# relayBoardSMD_RelayBottom.net
KiCad netlist of a schematic drawn in EAGLE
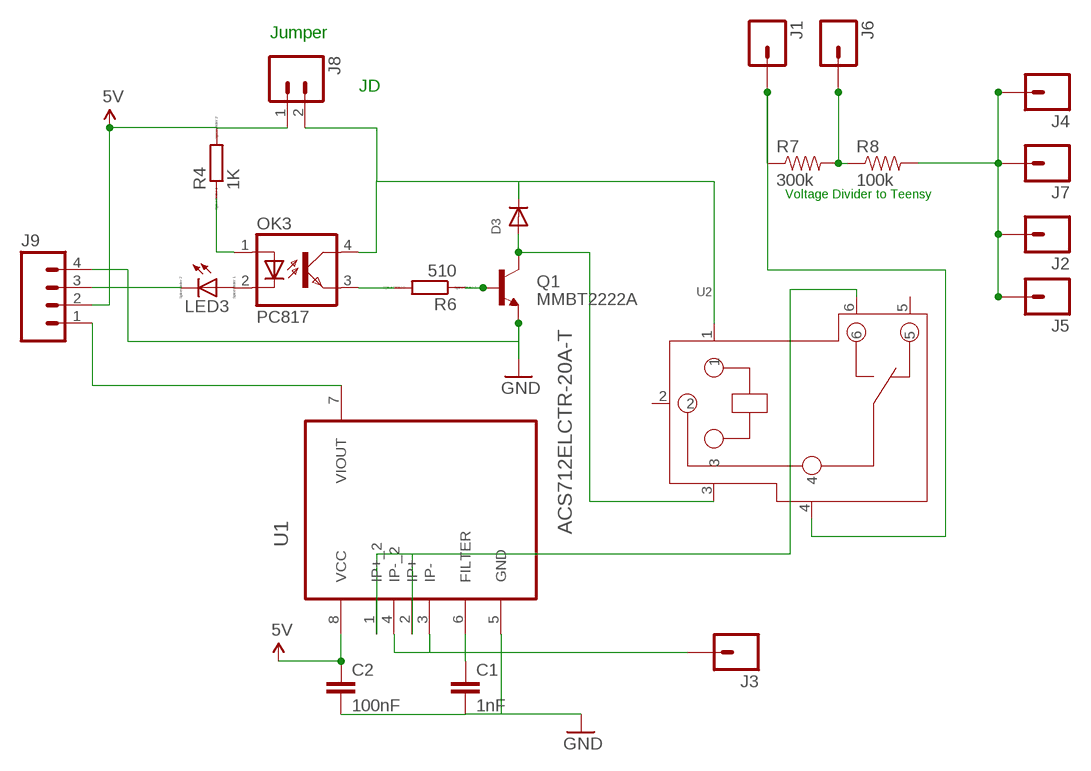
[diagram p0: schematic, sheet 1]

(export (version "E")
  (design (tool "Eeschema 10.0.6"))
  (components
    (comp (ref "C1")
      (value "1nF")
      (footprint "eagle-import:1206")
      (libsource (lib "eagle-import") (part "CAP1206"))
    )
    (comp (ref "C2")
      (value "100nF")
      (footprint "eagle-import:1206")
      (libsource (lib "eagle-import") (part "CAP1206"))
    )
    (comp (ref "D3")
      (value "DIODEDO-1N4148")
      (footprint "eagle-import:DO-1N4148")
      (libsource (lib "eagle-import") (part "DIODEDO-1N4148"))
    )
    (comp (ref "J1")
      (value "M01NOSILK-KIT")
      (footprint "eagle-import:1X01NS-KIT")
      (libsource (lib "eagle-import") (part "M01NOSILK-KIT"))
    )
    (comp (ref "J2")
      (value "M01NOSILK-KIT")
      (footprint "eagle-import:1X01NS-KIT")
      (libsource (lib "eagle-import") (part "M01NOSILK-KIT"))
    )
    (comp (ref "J3")
      (value "M01NOSILK-KIT")
      (footprint "eagle-import:1X01NS-KIT")
      (libsource (lib "eagle-import") (part "M01NOSILK-KIT"))
    )
    (comp (ref "J4")
      (value "M01NOSILK-KIT")
      (footprint "eagle-import:1X01NS-KIT")
      (libsource (lib "eagle-import") (part "M01NOSILK-KIT"))
    )
    (comp (ref "J5")
      (value "M01NOSILK-KIT")
      (footprint "eagle-import:1X01NS-KIT")
      (libsource (lib "eagle-import") (part "M01NOSILK-KIT"))
    )
    (comp (ref "J6")
      (value "M01NOSILK-KIT")
      (footprint "eagle-import:1X01NS-KIT")
      (libsource (lib "eagle-import") (part "M01NOSILK-KIT"))
    )
    (comp (ref "J7")
      (value "M01NOSILK-KIT")
      (footprint "eagle-import:1X01NS-KIT")
      (libsource (lib "eagle-import") (part "M01NOSILK-KIT"))
    )
    (comp (ref "J8")
      (value "M02LOCK_LONGPADS")
      (footprint "eagle-import:1X02_LOCK_LONGPADS")
      (libsource (lib "eagle-import") (part "M02LOCK_LONGPADS"))
    )
    (comp (ref "J9")
      (value "M04LOCK_LONGPADS")
      (footprint "eagle-import:1X04_LOCK_LONGPADS")
      (libsource (lib "eagle-import") (part "M04LOCK_LONGPADS"))
    )
    (comp (ref "LED3")
      (value "LED_E")
      (footprint "eagle-import:LED_1206")
      (libsource (lib "eagle-import") (part "LED_E"))
    )
    (comp (ref "OK3")
      (value "PC817")
      (footprint "eagle-import:DIL04")
      (fields (field (name "MPN") "PC817X4J000F"))
      (libsource (lib "eagle-import") (part "PC817"))
    )
    (comp (ref "Q1")
      (value "MMBT2222A")
      (footprint "eagle-import:SOT23-3")
      (libsource (lib "eagle-import") (part "TRANSISTOR_NPNMMBT2222A"))
    )
    (comp (ref "R4")
      (value "1K")
      (footprint "eagle-import:R1206")
      (libsource (lib "eagle-import") (part "RR1206"))
    )
    (comp (ref "R6")
      (value "510")
      (footprint "eagle-import:R1206")
      (libsource (lib "eagle-import") (part "RR1206"))
    )
    (comp (ref "R7")
      (value "300k")
      (footprint "eagle-import:1206")
      (libsource (lib "eagle-import") (part "RESISTOR1206"))
    )
    (comp (ref "R8")
      (value "100k")
      (footprint "eagle-import:1206")
      (libsource (lib "eagle-import") (part "RESISTOR1206"))
    )
    (comp (ref "U1")
      (value "ACS712ELCTR-20A-T")
      (footprint "eagle-import:SOIC127P600X175-8N")
      (libsource (lib "eagle-import") (part "ACS712ELCTR-20A-T"))
    )
    (comp (ref "U2")
      (value "RELAY-SLA-05VDC-SL-C")
      (footprint "eagle-import:6P-19.8H")
      (libsource (lib "eagle-import") (part "RELAY-SLA-05VDC-SL-C"))
    )
  )
  (nets
    (net (code "1") (name "5V") (class "Default")
      (node (ref "C2") (pin "1") (pinfunction "1_1") (pintype "passive"))
      (node (ref "J8") (pin "1") (pinfunction "1_1") (pintype "passive"))
      (node (ref "J9") (pin "2") (pinfunction "2_2") (pintype "passive"))
      (node (ref "R4") (pin "2") (pinfunction "2_2") (pintype "passive"))
      (node (ref "U1") (pin "8") (pinfunction "VCC_8") (pintype "power_in"))
    )
    (net (code "2") (name "GND") (class "Default")
      (node (ref "C1") (pin "2") (pinfunction "2_2") (pintype "passive"))
      (node (ref "C2") (pin "2") (pinfunction "2_2") (pintype "passive"))
      (node (ref "J9") (pin "4") (pinfunction "4_4") (pintype "passive"))
      (node (ref "Q1") (pin "2") (pinfunction "E_2") (pintype "passive"))
      (node (ref "U1") (pin "5") (pinfunction "GND_5") (pintype "passive"))
    )
    (net (code "3") (name "Net-(J1-Pad1)") (class "Default")
      (node (ref "J1") (pin "1") (pinfunction "1_1") (pintype "passive"))
      (node (ref "R7") (pin "1") (pinfunction "1_1") (pintype "passive"))
      (node (ref "U2") (pin "4") (pinfunction "4_4") (pintype "bidirectional"))
    )
    (net (code "4") (name "Net-(J2-Pad1)") (class "Default")
      (node (ref "J2") (pin "1") (pinfunction "1_1") (pintype "passive"))
      (node (ref "J4") (pin "1") (pinfunction "1_1") (pintype "passive"))
      (node (ref "J5") (pin "1") (pinfunction "1_1") (pintype "passive"))
      (node (ref "J7") (pin "1") (pinfunction "1_1") (pintype "passive"))
      (node (ref "R8") (pin "2") (pinfunction "2_2") (pintype "passive"))
    )
    (net (code "5") (name "Net-(J6-Pad1)") (class "Default")
      (node (ref "J6") (pin "1") (pinfunction "1_1") (pintype "passive"))
      (node (ref "R7") (pin "2") (pinfunction "2_2") (pintype "passive"))
      (node (ref "R8") (pin "1") (pinfunction "1_1") (pintype "passive"))
    )
    (net (code "6") (name "Net-(J9-Pad3)") (class "Default")
      (node (ref "J9") (pin "3") (pinfunction "3_3") (pintype "passive"))
      (node (ref "LED3") (pin "C") (pinfunction "C_C") (pintype "passive"))
    )
    (net (code "7") (name "Net-(OK3-A)") (class "Default")
      (node (ref "OK3") (pin "1") (pinfunction "A_1") (pintype "passive"))
      (node (ref "R4") (pin "1") (pinfunction "1_1") (pintype "passive"))
    )
    (net (code "8") (name "Net-(OK3-C)") (class "Default")
      (node (ref "LED3") (pin "A") (pinfunction "A_A") (pintype "passive"))
      (node (ref "OK3") (pin "2") (pinfunction "C_2") (pintype "passive"))
    )
    (net (code "9") (name "Net-(OK3-COL)") (class "Default")
      (node (ref "D3") (pin "C") (pinfunction "C_C") (pintype "passive"))
      (node (ref "J8") (pin "2") (pinfunction "2_2") (pintype "passive"))
      (node (ref "OK3") (pin "4") (pinfunction "COL_4") (pintype "passive"))
      (node (ref "U2") (pin "1") (pinfunction "1_1") (pintype "bidirectional"))
    )
    (net (code "10") (name "Net-(OK3-EMIT)") (class "Default")
      (node (ref "OK3") (pin "3") (pinfunction "EMIT_3") (pintype "passive"))
      (node (ref "R6") (pin "2") (pinfunction "2_2") (pintype "passive"))
    )
    (net (code "11") (name "Net-(Q1-B)") (class "Default")
      (node (ref "Q1") (pin "1") (pinfunction "B_1") (pintype "passive"))
      (node (ref "R6") (pin "1") (pinfunction "1_1") (pintype "passive"))
    )
    (net (code "12") (name "Net-(Q1-C)") (class "Default")
      (node (ref "D3") (pin "A") (pinfunction "A_A") (pintype "passive"))
      (node (ref "Q1") (pin "3") (pinfunction "C_3") (pintype "passive"))
      (node (ref "U2") (pin "3") (pinfunction "3_3") (pintype "bidirectional"))
    )
    (net (code "13") (name "Net-(U1-FILTER)") (class "Default")
      (node (ref "C1") (pin "1") (pinfunction "1_1") (pintype "passive"))
      (node (ref "U1") (pin "6") (pinfunction "FILTER_6") (pintype "input"))
    )
    (net (code "14") (name "Net-(U1-IP+)") (class "Default")
      (node (ref "U1") (pin "1") (pinfunction "IP+_2_1") (pintype "input"))
      (node (ref "U1") (pin "2") (pinfunction "IP+_2") (pintype "input"))
      (node (ref "U2") (pin "6") (pinfunction "6_6") (pintype "bidirectional"))
    )
    (net (code "15") (name "Net-(U1-IP-)") (class "Default")
      (node (ref "J3") (pin "1") (pinfunction "1_1") (pintype "passive"))
      (node (ref "U1") (pin "3") (pinfunction "IP-_3") (pintype "input"))
      (node (ref "U1") (pin "4") (pinfunction "IP-_2_4") (pintype "input"))
    )
    (net (code "16") (name "Net-(U1-VIOUT)") (class "Default")
      (node (ref "J9") (pin "1") (pinfunction "1_1") (pintype "passive"))
      (node (ref "U1") (pin "7") (pinfunction "VIOUT_7") (pintype "output"))
    )
    (net (code "17") (name "unconnected-(U2-Pad2)") (class "Default")
      (node (ref "U2") (pin "2") (pinfunction "2_2") (pintype "bidirectional"))
    )
    (net (code "18") (name "unconnected-(U2-Pad5)") (class "Default")
      (node (ref "U2") (pin "5") (pinfunction "5_5") (pintype "bidirectional"))
    )
  )
)
